# OSPLC2_2_IO1.net
KiCad netlist of a schematic drawn in Altium Designer
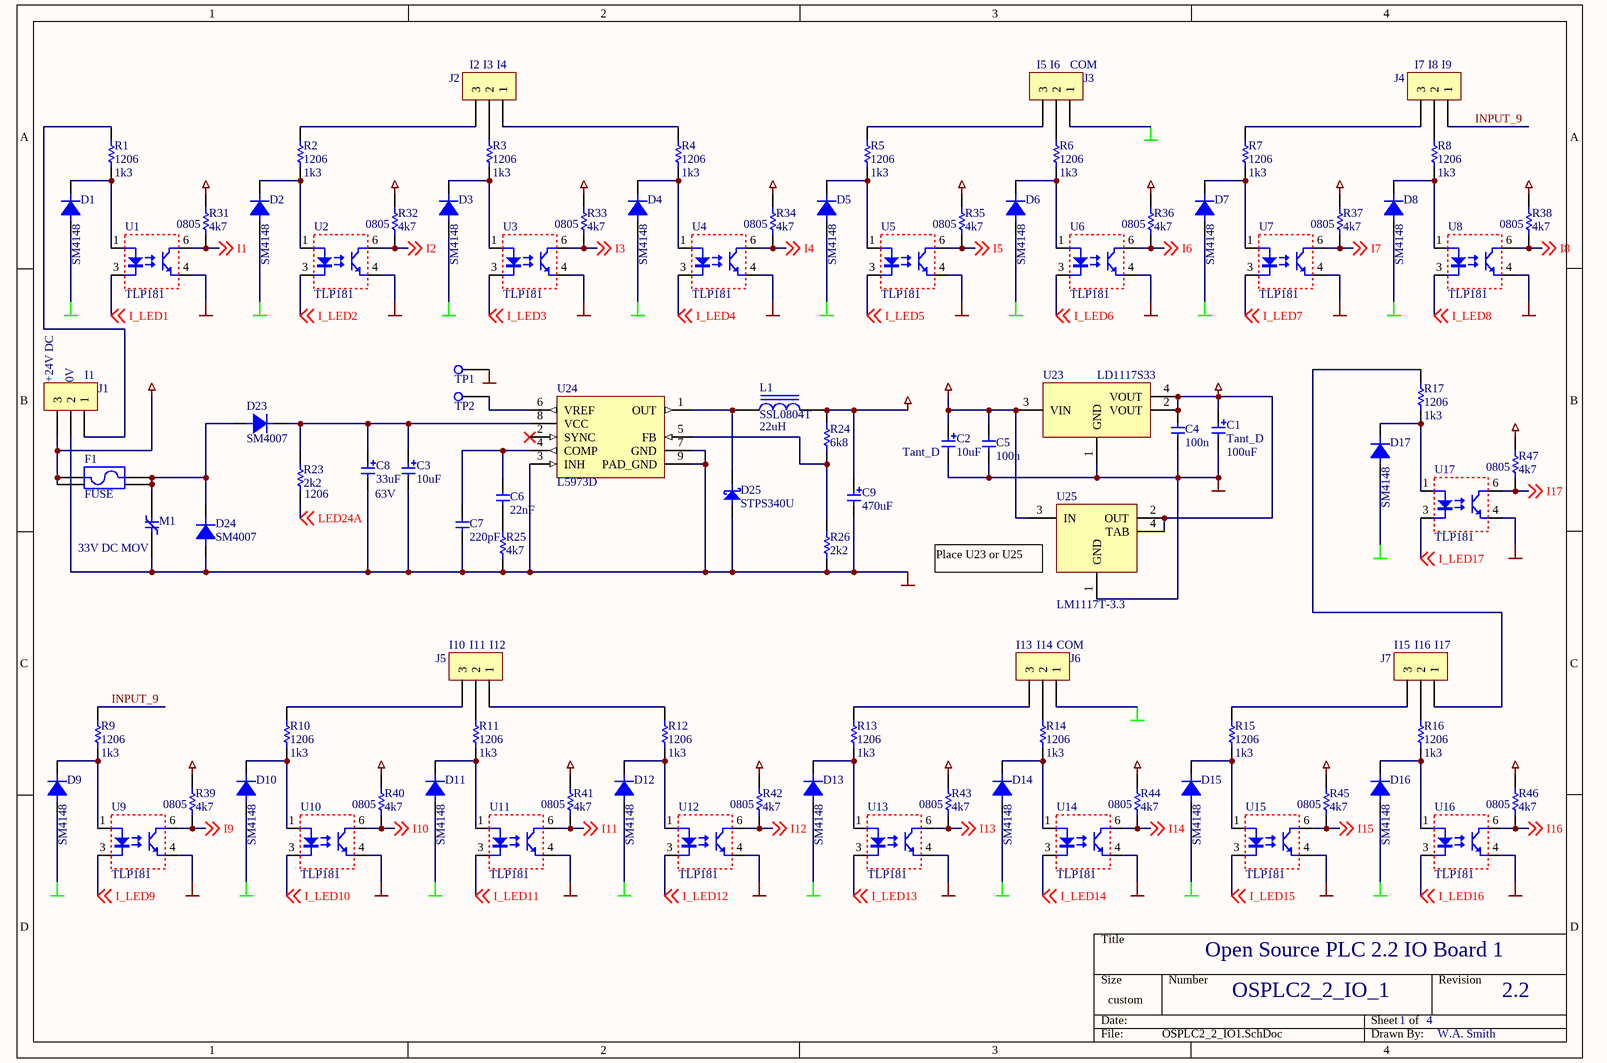
[diagram p0: OSPLC2_2_IO1.SchDoc]

(export (version "E")
  (design (tool "Eeschema 10.0.6"))
  (components
    (comp (ref "C1")
      (value "Tant_D")
      (footprint "CAP_TANT_D")
      (description "Tantalum Capacitor, D package")
      (fields (field (name "ALTIUM_VALUE") "100uF"))
      (libsource (lib "Integrated Comp_lib") (part "CAP_TANT_D"))
    )
    (comp (ref "C2")
      (value "Tant_D")
      (footprint "CAP_TANT_D")
      (description "Tantalum Capacitor, D package")
      (fields (field (name "ALTIUM_VALUE") "10uF"))
      (libsource (lib "Integrated Comp_lib") (part "CAP_TANT_D"))
    )
    (comp (ref "C3")
      (value "CAP_100_RP")
      (footprint "CAP_100_RP")
      (description "Electrolytic cap, 100 mil pitch")
      (fields (field (name "ALTIUM_VALUE") "10uF"))
      (libsource (lib "Integrated Comp_lib") (part "CAP_100_RP"))
    )
    (comp (ref "C4")
      (value "0805")
      (footprint "0805")
      (description "0805 footprint non-polarised capacitor")
      (fields (field (name "ALTIUM_VALUE") "100n"))
      (libsource (lib "Integrated Comp_lib") (part "CAP_0805"))
    )
    (comp (ref "C5")
      (value "0805")
      (footprint "0805")
      (description "0805 footprint non-polarised capacitor")
      (fields (field (name "ALTIUM_VALUE") "100n"))
      (libsource (lib "Integrated Comp_lib") (part "CAP_0805"))
    )
    (comp (ref "C6")
      (value "0805")
      (footprint "0805")
      (description "0805 footprint non-polarised capacitor")
      (fields (field (name "ALTIUM_VALUE") "22nF"))
      (libsource (lib "Integrated Comp_lib") (part "CAP_0805"))
    )
    (comp (ref "C7")
      (value "0805")
      (footprint "0805")
      (description "0805 footprint non-polarised capacitor")
      (fields (field (name "ALTIUM_VALUE") "220pF"))
      (libsource (lib "Integrated Comp_lib") (part "CAP_0805"))
    )
    (comp (ref "C8")
      (value "63V")
      (footprint "CAP_100_RP")
      (description "Electrolytic cap, 100 mil pitch")
      (fields (field (name "ALTIUM_VALUE") "33uF"))
      (libsource (lib "Integrated Comp_lib") (part "CAP_100_RP"))
    )
    (comp (ref "C9")
      (value "CAP_200_RP")
      (footprint "CAP_200_RP")
      (description "Radial Electrolytic Capacitor, 200 thou pin spacing")
      (fields (field (name "ALTIUM_VALUE") "470uF"))
      (libsource (lib "Integrated Comp_lib") (part "CAP_200_RP"))
    )
    (comp (ref "D1")
      (value "SM4148")
      (footprint "MELF-R2/X1.6")
      (description "SMT 1N4148 diode")
      (libsource (lib "ARM_projects") (part "SM4148"))
    )
    (comp (ref "D2")
      (value "SM4148")
      (footprint "MELF-R2/X1.6")
      (description "SMT 1N4148 diode")
      (libsource (lib "ARM_projects") (part "SM4148"))
    )
    (comp (ref "D3")
      (value "SM4148")
      (footprint "MELF-R2/X1.6")
      (description "SMT 1N4148 diode")
      (libsource (lib "ARM_projects") (part "SM4148"))
    )
    (comp (ref "D4")
      (value "SM4148")
      (footprint "MELF-R2/X1.6")
      (description "SMT 1N4148 diode")
      (libsource (lib "ARM_projects") (part "SM4148"))
    )
    (comp (ref "D5")
      (value "SM4148")
      (footprint "MELF-R2/X1.6")
      (description "SMT 1N4148 diode")
      (libsource (lib "ARM_projects") (part "SM4148"))
    )
    (comp (ref "D6")
      (value "SM4148")
      (footprint "MELF-R2/X1.6")
      (description "SMT 1N4148 diode")
      (libsource (lib "ARM_projects") (part "SM4148"))
    )
    (comp (ref "D7")
      (value "SM4148")
      (footprint "MELF-R2/X1.6")
      (description "SMT 1N4148 diode")
      (libsource (lib "ARM_projects") (part "SM4148"))
    )
    (comp (ref "D8")
      (value "SM4148")
      (footprint "MELF-R2/X1.6")
      (description "SMT 1N4148 diode")
      (libsource (lib "ARM_projects") (part "SM4148"))
    )
    (comp (ref "D9")
      (value "SM4148")
      (footprint "MELF-R2/X1.6")
      (description "SMT 1N4148 diode")
      (libsource (lib "ARM_projects") (part "SM4148"))
    )
    (comp (ref "D10")
      (value "SM4148")
      (footprint "MELF-R2/X1.6")
      (description "SMT 1N4148 diode")
      (libsource (lib "ARM_projects") (part "SM4148"))
    )
    (comp (ref "D11")
      (value "SM4148")
      (footprint "MELF-R2/X1.6")
      (description "SMT 1N4148 diode")
      (libsource (lib "ARM_projects") (part "SM4148"))
    )
    (comp (ref "D12")
      (value "SM4148")
      (footprint "MELF-R2/X1.6")
      (description "SMT 1N4148 diode")
      (libsource (lib "ARM_projects") (part "SM4148"))
    )
    (comp (ref "D13")
      (value "SM4148")
      (footprint "MELF-R2/X1.6")
      (description "SMT 1N4148 diode")
      (libsource (lib "ARM_projects") (part "SM4148"))
    )
    (comp (ref "D14")
      (value "SM4148")
      (footprint "MELF-R2/X1.6")
      (description "SMT 1N4148 diode")
      (libsource (lib "ARM_projects") (part "SM4148"))
    )
    (comp (ref "D15")
      (value "SM4148")
      (footprint "MELF-R2/X1.6")
      (description "SMT 1N4148 diode")
      (libsource (lib "ARM_projects") (part "SM4148"))
    )
    (comp (ref "D16")
      (value "SM4148")
      (footprint "MELF-R2/X1.6")
      (description "SMT 1N4148 diode")
      (libsource (lib "ARM_projects") (part "SM4148"))
    )
    (comp (ref "D17")
      (value "SM4148")
      (footprint "MELF-R2/X1.6")
      (description "SMT 1N4148 diode")
      (libsource (lib "ARM_projects") (part "SM4148"))
    )
    (comp (ref "D23")
      (value "SM4007")
      (footprint "MELF-2.2x2.5")
      (description "1A, 1000V MELF Rectifier")
      (libsource (lib "ARM_projects") (part "SM4007"))
    )
    (comp (ref "D24")
      (value "SM4007")
      (footprint "MELF-2.2x2.5")
      (description "1A, 1000V MELF Rectifier")
      (libsource (lib "ARM_projects") (part "SM4007"))
    )
    (comp (ref "D25")
      (value "STPS340U")
      (footprint "STPS2L25U")
      (description "Power Schottky rectifier, ST")
      (libsource (lib "ARM_projects") (part "STPS340U"))
    )
    (comp (ref "F1")
      (value "FUSE")
      (footprint "FUSE_MULT")
      (description "Fuse holder or Fuse clips for 20mm fuse")
      (libsource (lib "ARM_projects") (part "FUSE_MULTI"))
    )
    (comp (ref "J1")
      (value "PCB TERMINAL")
      (footprint "TERMINAL_3WAY_5MM")
      (description "5mm spaced PCB terminal, 3 pole")
      (libsource (lib "ARM_projects") (part "TERMINAL_3WAY_5MM"))
    )
    (comp (ref "J2")
      (value "PCB TERMINAL")
      (footprint "TERMINAL_3WAY_5MM")
      (description "5mm spaced PCB terminal, 3 pole")
      (libsource (lib "ARM_projects") (part "TERMINAL_3WAY_5MM"))
    )
    (comp (ref "J3")
      (value "PCB TERMINAL")
      (footprint "TERMINAL_3WAY_5MM")
      (description "5mm spaced PCB terminal, 3 pole")
      (libsource (lib "ARM_projects") (part "TERMINAL_3WAY_5MM"))
    )
    (comp (ref "J4")
      (value "PCB TERMINAL")
      (footprint "TERMINAL_3WAY_5MM")
      (description "5mm spaced PCB terminal, 3 pole")
      (libsource (lib "ARM_projects") (part "TERMINAL_3WAY_5MM"))
    )
    (comp (ref "J5")
      (value "PCB TERMINAL")
      (footprint "TERMINAL_3WAY_5MM")
      (description "5mm spaced PCB terminal, 3 pole")
      (libsource (lib "ARM_projects") (part "TERMINAL_3WAY_5MM"))
    )
    (comp (ref "J6")
      (value "PCB TERMINAL")
      (footprint "TERMINAL_3WAY_5MM")
      (description "5mm spaced PCB terminal, 3 pole")
      (libsource (lib "ARM_projects") (part "TERMINAL_3WAY_5MM"))
    )
    (comp (ref "J7")
      (value "PCB TERMINAL")
      (footprint "TERMINAL_3WAY_5MM")
      (description "5mm spaced PCB terminal, 3 pole")
      (libsource (lib "ARM_projects") (part "TERMINAL_3WAY_5MM"))
    )
    (comp (ref "L1")
      (value "SSL0804T")
      (footprint "SSL0804")
      (description "Yageo SMD Power Inductor")
      (fields (field (name "ALTIUM_UNNAMED_1") "22uH"))
      (libsource (lib "ARM_projects") (part "SSL0804T"))
    )
    (comp (ref "M1")
      (value "33V DC MOV")
      (footprint "MOV_7.6mm")
      (description "Metal Oxide Varistor")
      (libsource (lib "ARM_projects") (part "MOV_7.6MM"))
    )
    (comp (ref "R1")
      (value "1206")
      (footprint "1206")
      (description "1206 footprint resistor")
      (fields (field (name "ALTIUM_VALUE") "1k3"))
      (libsource (lib "Integrated Comp_lib") (part "RES_1206"))
    )
    (comp (ref "R2")
      (value "1206")
      (footprint "1206")
      (description "1206 footprint resistor")
      (fields (field (name "ALTIUM_VALUE") "1k3"))
      (libsource (lib "Integrated Comp_lib") (part "RES_1206"))
    )
    (comp (ref "R3")
      (value "1206")
      (footprint "1206")
      (description "1206 footprint resistor")
      (fields (field (name "ALTIUM_VALUE") "1k3"))
      (libsource (lib "Integrated Comp_lib") (part "RES_1206"))
    )
    (comp (ref "R4")
      (value "1206")
      (footprint "1206")
      (description "1206 footprint resistor")
      (fields (field (name "ALTIUM_VALUE") "1k3"))
      (libsource (lib "Integrated Comp_lib") (part "RES_1206"))
    )
    (comp (ref "R5")
      (value "1206")
      (footprint "1206")
      (description "1206 footprint resistor")
      (fields (field (name "ALTIUM_VALUE") "1k3"))
      (libsource (lib "Integrated Comp_lib") (part "RES_1206"))
    )
    (comp (ref "R6")
      (value "1206")
      (footprint "1206")
      (description "1206 footprint resistor")
      (fields (field (name "ALTIUM_VALUE") "1k3"))
      (libsource (lib "Integrated Comp_lib") (part "RES_1206"))
    )
    (comp (ref "R7")
      (value "1206")
      (footprint "1206")
      (description "1206 footprint resistor")
      (fields (field (name "ALTIUM_VALUE") "1k3"))
      (libsource (lib "Integrated Comp_lib") (part "RES_1206"))
    )
    (comp (ref "R8")
      (value "1206")
      (footprint "1206")
      (description "1206 footprint resistor")
      (fields (field (name "ALTIUM_VALUE") "1k3"))
      (libsource (lib "Integrated Comp_lib") (part "RES_1206"))
    )
    (comp (ref "R9")
      (value "1206")
      (footprint "1206")
      (description "1206 footprint resistor")
      (fields (field (name "ALTIUM_VALUE") "1k3"))
      (libsource (lib "Integrated Comp_lib") (part "RES_1206"))
    )
    (comp (ref "R10")
      (value "1206")
      (footprint "1206")
      (description "1206 footprint resistor")
      (fields (field (name "ALTIUM_VALUE") "1k3"))
      (libsource (lib "Integrated Comp_lib") (part "RES_1206"))
    )
    (comp (ref "R11")
      (value "1206")
      (footprint "1206")
      (description "1206 footprint resistor")
      (fields (field (name "ALTIUM_VALUE") "1k3"))
      (libsource (lib "Integrated Comp_lib") (part "RES_1206"))
    )
    (comp (ref "R12")
      (value "1206")
      (footprint "1206")
      (description "1206 footprint resistor")
      (fields (field (name "ALTIUM_VALUE") "1k3"))
      (libsource (lib "Integrated Comp_lib") (part "RES_1206"))
    )
    (comp (ref "R13")
      (value "1206")
      (footprint "1206")
      (description "1206 footprint resistor")
      (fields (field (name "ALTIUM_VALUE") "1k3"))
      (libsource (lib "Integrated Comp_lib") (part "RES_1206"))
    )
    (comp (ref "R14")
      (value "1206")
      (footprint "1206")
      (description "1206 footprint resistor")
      (fields (field (name "ALTIUM_VALUE") "1k3"))
      (libsource (lib "Integrated Comp_lib") (part "RES_1206"))
    )
    (comp (ref "R15")
      (value "1206")
      (footprint "1206")
      (description "1206 footprint resistor")
      (fields (field (name "ALTIUM_VALUE") "1k3"))
      (libsource (lib "Integrated Comp_lib") (part "RES_1206"))
    )
    (comp (ref "R16")
      (value "1206")
      (footprint "1206")
      (description "1206 footprint resistor")
      (fields (field (name "ALTIUM_VALUE") "1k3"))
      (libsource (lib "Integrated Comp_lib") (part "RES_1206"))
    )
    (comp (ref "R17")
      (value "1206")
      (footprint "1206")
      (description "1206 footprint resistor")
      (fields (field (name "ALTIUM_VALUE") "1k3"))
      (libsource (lib "Integrated Comp_lib") (part "RES_1206"))
    )
    (comp (ref "R23")
      (value "1206")
      (footprint "1206")
      (description "1206 footprint resistor")
      (fields (field (name "ALTIUM_VALUE") "2k2"))
      (libsource (lib "Integrated Comp_lib") (part "RES_1206"))
    )
    (comp (ref "R24")
      (value "0805")
      (footprint "0805")
      (description "0805 footprint resistor")
      (fields (field (name "ALTIUM_VALUE") "6k8"))
      (libsource (lib "Integrated Comp_lib") (part "RES_0805"))
    )
    (comp (ref "R25")
      (value "0805")
      (footprint "0805")
      (description "0805 footprint resistor")
      (fields (field (name "ALTIUM_VALUE") "4k7"))
      (libsource (lib "Integrated Comp_lib") (part "RES_0805"))
    )
    (comp (ref "R26")
      (value "0805")
      (footprint "0805")
      (description "0805 footprint resistor")
      (fields (field (name "ALTIUM_VALUE") "2k2"))
      (libsource (lib "Integrated Comp_lib") (part "RES_0805"))
    )
    (comp (ref "R31")
      (value "0805")
      (footprint "0805")
      (description "0805 footprint resistor")
      (fields (field (name "ALTIUM_VALUE") "4k7"))
      (libsource (lib "Integrated Comp_lib") (part "RES_0805"))
    )
    (comp (ref "R32")
      (value "0805")
      (footprint "0805")
      (description "0805 footprint resistor")
      (fields (field (name "ALTIUM_VALUE") "4k7"))
      (libsource (lib "Integrated Comp_lib") (part "RES_0805"))
    )
    (comp (ref "R33")
      (value "0805")
      (footprint "0805")
      (description "0805 footprint resistor")
      (fields (field (name "ALTIUM_VALUE") "4k7"))
      (libsource (lib "Integrated Comp_lib") (part "RES_0805"))
    )
    (comp (ref "R34")
      (value "0805")
      (footprint "0805")
      (description "0805 footprint resistor")
      (fields (field (name "ALTIUM_VALUE") "4k7"))
      (libsource (lib "Integrated Comp_lib") (part "RES_0805"))
    )
    (comp (ref "R35")
      (value "0805")
      (footprint "0805")
      (description "0805 footprint resistor")
      (fields (field (name "ALTIUM_VALUE") "4k7"))
      (libsource (lib "Integrated Comp_lib") (part "RES_0805"))
    )
    (comp (ref "R36")
      (value "0805")
      (footprint "0805")
      (description "0805 footprint resistor")
      (fields (field (name "ALTIUM_VALUE") "4k7"))
      (libsource (lib "Integrated Comp_lib") (part "RES_0805"))
    )
    (comp (ref "R37")
      (value "0805")
      (footprint "0805")
      (description "0805 footprint resistor")
      (fields (field (name "ALTIUM_VALUE") "4k7"))
      (libsource (lib "Integrated Comp_lib") (part "RES_0805"))
    )
    (comp (ref "R38")
      (value "0805")
      (footprint "0805")
      (description "0805 footprint resistor")
      (fields (field (name "ALTIUM_VALUE") "4k7"))
      (libsource (lib "Integrated Comp_lib") (part "RES_0805"))
    )
    (comp (ref "R39")
      (value "0805")
      (footprint "0805")
      (description "0805 footprint resistor")
      (fields (field (name "ALTIUM_VALUE") "4k7"))
      (libsource (lib "Integrated Comp_lib") (part "RES_0805"))
    )
    (comp (ref "R40")
      (value "0805")
      (footprint "0805")
      (description "0805 footprint resistor")
      (fields (field (name "ALTIUM_VALUE") "4k7"))
      (libsource (lib "Integrated Comp_lib") (part "RES_0805"))
    )
    (comp (ref "R41")
      (value "0805")
      (footprint "0805")
      (description "0805 footprint resistor")
      (fields (field (name "ALTIUM_VALUE") "4k7"))
      (libsource (lib "Integrated Comp_lib") (part "RES_0805"))
    )
    (comp (ref "R42")
      (value "0805")
      (footprint "0805")
      (description "0805 footprint resistor")
      (fields (field (name "ALTIUM_VALUE") "4k7"))
      (libsource (lib "Integrated Comp_lib") (part "RES_0805"))
    )
    (comp (ref "R43")
      (value "0805")
      (footprint "0805")
      (description "0805 footprint resistor")
      (fields (field (name "ALTIUM_VALUE") "4k7"))
      (libsource (lib "Integrated Comp_lib") (part "RES_0805"))
    )
    (comp (ref "R44")
      (value "0805")
      (footprint "0805")
      (description "0805 footprint resistor")
      (fields (field (name "ALTIUM_VALUE") "4k7"))
      (libsource (lib "Integrated Comp_lib") (part "RES_0805"))
    )
    (comp (ref "R45")
      (value "0805")
      (footprint "0805")
      (description "0805 footprint resistor")
      (fields (field (name "ALTIUM_VALUE") "4k7"))
      (libsource (lib "Integrated Comp_lib") (part "RES_0805"))
    )
    (comp (ref "R46")
      (value "0805")
      (footprint "0805")
      (description "0805 footprint resistor")
      (fields (field (name "ALTIUM_VALUE") "4k7"))
      (libsource (lib "Integrated Comp_lib") (part "RES_0805"))
    )
    (comp (ref "R47")
      (value "0805")
      (footprint "0805")
      (description "0805 footprint resistor")
      (fields (field (name "ALTIUM_VALUE") "4k7"))
      (libsource (lib "Integrated Comp_lib") (part "RES_0805"))
    )
    (comp (ref "TP1")
      (value "TEST POINT")
      (footprint "TEST_POINT_TH")
      (description "Through hole test point")
      (libsource (lib "ARM_projects") (part "TEST_POINT_TH"))
    )
    (comp (ref "TP2")
      (value "TEST POINT")
      (footprint "TEST_POINT_TH")
      (description "Through hole test point")
      (libsource (lib "ARM_projects") (part "TEST_POINT_TH"))
    )
    (comp (ref "U1")
      (value "TLP181")
      (footprint "SOP4_2.54")
      (description "Toshiba Photocoupler")
      (libsource (lib "Integrated Comp_lib") (part "TLP181"))
    )
    (comp (ref "U2")
      (value "TLP181")
      (footprint "SOP4_2.54")
      (description "Toshiba Photocoupler")
      (libsource (lib "Integrated Comp_lib") (part "TLP181"))
    )
    (comp (ref "U3")
      (value "TLP181")
      (footprint "SOP4_2.54")
      (description "Toshiba Photocoupler")
      (libsource (lib "Integrated Comp_lib") (part "TLP181"))
    )
    (comp (ref "U4")
      (value "TLP181")
      (footprint "SOP4_2.54")
      (description "Toshiba Photocoupler")
      (libsource (lib "Integrated Comp_lib") (part "TLP181"))
    )
    (comp (ref "U5")
      (value "TLP181")
      (footprint "SOP4_2.54")
      (description "Toshiba Photocoupler")
      (libsource (lib "Integrated Comp_lib") (part "TLP181"))
    )
    (comp (ref "U6")
      (value "TLP181")
      (footprint "SOP4_2.54")
      (description "Toshiba Photocoupler")
      (libsource (lib "Integrated Comp_lib") (part "TLP181"))
    )
    (comp (ref "U7")
      (value "TLP181")
      (footprint "SOP4_2.54")
      (description "Toshiba Photocoupler")
      (libsource (lib "Integrated Comp_lib") (part "TLP181"))
    )
    (comp (ref "U8")
      (value "TLP181")
      (footprint "SOP4_2.54")
      (description "Toshiba Photocoupler")
      (libsource (lib "Integrated Comp_lib") (part "TLP181"))
    )
    (comp (ref "U9")
      (value "TLP181")
      (footprint "SOP4_2.54")
      (description "Toshiba Photocoupler")
      (libsource (lib "Integrated Comp_lib") (part "TLP181"))
    )
    (comp (ref "U10")
      (value "TLP181")
      (footprint "SOP4_2.54")
      (description "Toshiba Photocoupler")
      (libsource (lib "Integrated Comp_lib") (part "TLP181"))
    )
    (comp (ref "U11")
      (value "TLP181")
      (footprint "SOP4_2.54")
      (description "Toshiba Photocoupler")
      (libsource (lib "Integrated Comp_lib") (part "TLP181"))
    )
    (comp (ref "U12")
      (value "TLP181")
      (footprint "SOP4_2.54")
      (description "Toshiba Photocoupler")
      (libsource (lib "Integrated Comp_lib") (part "TLP181"))
    )
    (comp (ref "U13")
      (value "TLP181")
      (footprint "SOP4_2.54")
      (description "Toshiba Photocoupler")
      (libsource (lib "Integrated Comp_lib") (part "TLP181"))
    )
    (comp (ref "U14")
      (value "TLP181")
      (footprint "SOP4_2.54")
      (description "Toshiba Photocoupler")
      (libsource (lib "Integrated Comp_lib") (part "TLP181"))
    )
    (comp (ref "U15")
      (value "TLP181")
      (footprint "SOP4_2.54")
      (description "Toshiba Photocoupler")
      (libsource (lib "Integrated Comp_lib") (part "TLP181"))
    )
    (comp (ref "U16")
      (value "TLP181")
      (footprint "SOP4_2.54")
      (description "Toshiba Photocoupler")
      (libsource (lib "Integrated Comp_lib") (part "TLP181"))
    )
    (comp (ref "U17")
      (value "TLP181")
      (footprint "SOP4_2.54")
      (description "Toshiba Photocoupler")
      (libsource (lib "Integrated Comp_lib") (part "TLP181"))
    )
    (comp (ref "U23")
      (value "LD1117S33")
      (footprint "SOT-223")
      (description "ST 3.3V LDO regulator")
      (libsource (lib "ARM_projects") (part "LD1117S33"))
    )
    (comp (ref "U24")
      (value "L5973D")
      (footprint "ARM_projects:HSOP8")
      (description "ST 2.5A switch step down switching regulator")
      (libsource (lib "ARM_projects") (part "L5973D"))
    )
    (comp (ref "U25")
      (value "LM1117T-3.3")
      (footprint "TO-220_H")
      (description "National  800mA LDO regulator")
      (libsource (lib "Integrated Comp_lib") (part "LM1117T-3.3"))
    )
  )
  (nets
    (net (code "1") (name "/INPUT_9") (class "Default")
      (node (ref "J4") (pin "1") (pinfunction "1_1") (pintype "passive"))
      (node (ref "R9") (pin "2") (pinfunction "2_2") (pintype "passive"))
    )
    (net (code "2") (name "GND") (class "Default")
      (node (ref "C1") (pin "2") (pinfunction "2_2") (pintype "passive"))
      (node (ref "C2") (pin "2") (pinfunction "2_2") (pintype "passive"))
      (node (ref "C3") (pin "2") (pinfunction "2_2") (pintype "passive"))
      (node (ref "C4") (pin "2") (pinfunction "2_2") (pintype "passive"))
      (node (ref "C5") (pin "2") (pinfunction "2_2") (pintype "passive"))
      (node (ref "C7") (pin "1") (pinfunction "1_1") (pintype "passive"))
      (node (ref "C8") (pin "2") (pinfunction "2_2") (pintype "passive"))
      (node (ref "C9") (pin "2") (pinfunction "2_2") (pintype "passive"))
      (node (ref "D24") (pin "1") (pinfunction "A_1") (pintype "passive"))
      (node (ref "D25") (pin "2") (pinfunction "A_2") (pintype "passive"))
      (node (ref "J1") (pin "2") (pinfunction "2_2") (pintype "passive"))
      (node (ref "M1") (pin "1") (pinfunction "1_1") (pintype "passive"))
      (node (ref "R25") (pin "1") (pinfunction "1_1") (pintype "passive"))
      (node (ref "R26") (pin "1") (pinfunction "1_1") (pintype "passive"))
      (node (ref "TP1") (pin "1") (pinfunction "1_1") (pintype "passive"))
      (node (ref "U1") (pin "4") (pinfunction "4_4") (pintype "passive"))
      (node (ref "U10") (pin "4") (pinfunction "4_4") (pintype "passive"))
      (node (ref "U11") (pin "4") (pinfunction "4_4") (pintype "passive"))
      (node (ref "U12") (pin "4") (pinfunction "4_4") (pintype "passive"))
      (node (ref "U13") (pin "4") (pinfunction "4_4") (pintype "passive"))
      (node (ref "U14") (pin "4") (pinfunction "4_4") (pintype "passive"))
      (node (ref "U15") (pin "4") (pinfunction "4_4") (pintype "passive"))
      (node (ref "U16") (pin "4") (pinfunction "4_4") (pintype "passive"))
      (node (ref "U17") (pin "4") (pinfunction "4_4") (pintype "passive"))
      (node (ref "U2") (pin "4") (pinfunction "4_4") (pintype "passive"))
      (node (ref "U23") (pin "1") (pinfunction "GND_1") (pintype "power_in"))
      (node (ref "U24") (pin "3") (pinfunction "INH_3") (pintype "input"))
      (node (ref "U24") (pin "7") (pinfunction "GND_7") (pintype "power_in"))
      (node (ref "U24") (pin "9") (pinfunction "PAD_GND_9") (pintype "power_in"))
      (node (ref "U25") (pin "1") (pinfunction "GND_1") (pintype "power_in"))
      (node (ref "U3") (pin "4") (pinfunction "4_4") (pintype "passive"))
      (node (ref "U4") (pin "4") (pinfunction "4_4") (pintype "passive"))
      (node (ref "U5") (pin "4") (pinfunction "4_4") (pintype "passive"))
      (node (ref "U6") (pin "4") (pinfunction "4_4") (pintype "passive"))
      (node (ref "U7") (pin "4") (pinfunction "4_4") (pintype "passive"))
      (node (ref "U8") (pin "4") (pinfunction "4_4") (pintype "passive"))
      (node (ref "U9") (pin "4") (pinfunction "4_4") (pintype "passive"))
    )
    (net (code "3") (name "I1") (class "Default")
      (node (ref "R31") (pin "1") (pinfunction "1_1") (pintype "passive"))
      (node (ref "U1") (pin "6") (pinfunction "6_6") (pintype "passive"))
    )
    (net (code "4") (name "I2") (class "Default")
      (node (ref "R32") (pin "1") (pinfunction "1_1") (pintype "passive"))
      (node (ref "U2") (pin "6") (pinfunction "6_6") (pintype "passive"))
    )
    (net (code "5") (name "I3") (class "Default")
      (node (ref "R33") (pin "1") (pinfunction "1_1") (pintype "passive"))
      (node (ref "U3") (pin "6") (pinfunction "6_6") (pintype "passive"))
    )
    (net (code "6") (name "I4") (class "Default")
      (node (ref "R34") (pin "1") (pinfunction "1_1") (pintype "passive"))
      (node (ref "U4") (pin "6") (pinfunction "6_6") (pintype "passive"))
    )
    (net (code "7") (name "I5") (class "Default")
      (node (ref "R35") (pin "1") (pinfunction "1_1") (pintype "passive"))
      (node (ref "U5") (pin "6") (pinfunction "6_6") (pintype "passive"))
    )
    (net (code "8") (name "I6") (class "Default")
      (node (ref "R36") (pin "1") (pinfunction "1_1") (pintype "passive"))
      (node (ref "U6") (pin "6") (pinfunction "6_6") (pintype "passive"))
    )
    (net (code "9") (name "I7") (class "Default")
      (node (ref "R37") (pin "1") (pinfunction "1_1") (pintype "passive"))
      (node (ref "U7") (pin "6") (pinfunction "6_6") (pintype "passive"))
    )
    (net (code "10") (name "I8") (class "Default")
      (node (ref "R38") (pin "1") (pinfunction "1_1") (pintype "passive"))
      (node (ref "U8") (pin "6") (pinfunction "6_6") (pintype "passive"))
    )
    (net (code "11") (name "I9") (class "Default")
      (node (ref "R39") (pin "1") (pinfunction "1_1") (pintype "passive"))
      (node (ref "U9") (pin "6") (pinfunction "6_6") (pintype "passive"))
    )
    (net (code "12") (name "I10") (class "Default")
      (node (ref "R40") (pin "1") (pinfunction "1_1") (pintype "passive"))
      (node (ref "U10") (pin "6") (pinfunction "6_6") (pintype "passive"))
    )
    (net (code "13") (name "I11") (class "Default")
      (node (ref "R41") (pin "1") (pinfunction "1_1") (pintype "passive"))
      (node (ref "U11") (pin "6") (pinfunction "6_6") (pintype "passive"))
    )
    (net (code "14") (name "I12") (class "Default")
      (node (ref "R42") (pin "1") (pinfunction "1_1") (pintype "passive"))
      (node (ref "U12") (pin "6") (pinfunction "6_6") (pintype "passive"))
    )
    (net (code "15") (name "I13") (class "Default")
      (node (ref "R43") (pin "1") (pinfunction "1_1") (pintype "passive"))
      (node (ref "U13") (pin "6") (pinfunction "6_6") (pintype "passive"))
    )
    (net (code "16") (name "I14") (class "Default")
      (node (ref "R44") (pin "1") (pinfunction "1_1") (pintype "passive"))
      (node (ref "U14") (pin "6") (pinfunction "6_6") (pintype "passive"))
    )
    (net (code "17") (name "I15") (class "Default")
      (node (ref "R45") (pin "1") (pinfunction "1_1") (pintype "passive"))
      (node (ref "U15") (pin "6") (pinfunction "6_6") (pintype "passive"))
    )
    (net (code "18") (name "I16") (class "Default")
      (node (ref "R46") (pin "1") (pinfunction "1_1") (pintype "passive"))
      (node (ref "U16") (pin "6") (pinfunction "6_6") (pintype "passive"))
    )
    (net (code "19") (name "I17") (class "Default")
      (node (ref "R47") (pin "1") (pinfunction "1_1") (pintype "passive"))
      (node (ref "U17") (pin "6") (pinfunction "6_6") (pintype "passive"))
    )
    (net (code "20") (name "IN_GND") (class "Default")
      (node (ref "D1") (pin "1") (pinfunction "A_1") (pintype "passive"))
      (node (ref "D10") (pin "1") (pinfunction "A_1") (pintype "passive"))
      (node (ref "D11") (pin "1") (pinfunction "A_1") (pintype "passive"))
      (node (ref "D12") (pin "1") (pinfunction "A_1") (pintype "passive"))
      (node (ref "D13") (pin "1") (pinfunction "A_1") (pintype "passive"))
      (node (ref "D14") (pin "1") (pinfunction "A_1") (pintype "passive"))
      (node (ref "D15") (pin "1") (pinfunction "A_1") (pintype "passive"))
      (node (ref "D16") (pin "1") (pinfunction "A_1") (pintype "passive"))
      (node (ref "D17") (pin "1") (pinfunction "A_1") (pintype "passive"))
      (node (ref "D2") (pin "1") (pinfunction "A_1") (pintype "passive"))
      (node (ref "D3") (pin "1") (pinfunction "A_1") (pintype "passive"))
      (node (ref "D4") (pin "1") (pinfunction "A_1") (pintype "passive"))
      (node (ref "D5") (pin "1") (pinfunction "A_1") (pintype "passive"))
      (node (ref "D6") (pin "1") (pinfunction "A_1") (pintype "passive"))
      (node (ref "D7") (pin "1") (pinfunction "A_1") (pintype "passive"))
      (node (ref "D8") (pin "1") (pinfunction "A_1") (pintype "passive"))
      (node (ref "D9") (pin "1") (pinfunction "A_1") (pintype "passive"))
      (node (ref "J3") (pin "1") (pinfunction "1_1") (pintype "passive"))
      (node (ref "J6") (pin "1") (pinfunction "1_1") (pintype "passive"))
    )
    (net (code "21") (name "I_LED1") (class "Default")
      (node (ref "U1") (pin "3") (pinfunction "3_3") (pintype "passive"))
    )
    (net (code "22") (name "I_LED2") (class "Default")
      (node (ref "U2") (pin "3") (pinfunction "3_3") (pintype "passive"))
    )
    (net (code "23") (name "I_LED3") (class "Default")
      (node (ref "U3") (pin "3") (pinfunction "3_3") (pintype "passive"))
    )
    (net (code "24") (name "I_LED4") (class "Default")
      (node (ref "U4") (pin "3") (pinfunction "3_3") (pintype "passive"))
    )
    (net (code "25") (name "I_LED5") (class "Default")
      (node (ref "U5") (pin "3") (pinfunction "3_3") (pintype "passive"))
    )
    (net (code "26") (name "I_LED6") (class "Default")
      (node (ref "U6") (pin "3") (pinfunction "3_3") (pintype "passive"))
    )
    (net (code "27") (name "I_LED7") (class "Default")
      (node (ref "U7") (pin "3") (pinfunction "3_3") (pintype "passive"))
    )
    (net (code "28") (name "I_LED8") (class "Default")
      (node (ref "U8") (pin "3") (pinfunction "3_3") (pintype "passive"))
    )
    (net (code "29") (name "I_LED9") (class "Default")
      (node (ref "U9") (pin "3") (pinfunction "3_3") (pintype "passive"))
    )
    (net (code "30") (name "I_LED10") (class "Default")
      (node (ref "U10") (pin "3") (pinfunction "3_3") (pintype "passive"))
    )
    (net (code "31") (name "I_LED11") (class "Default")
      (node (ref "U11") (pin "3") (pinfunction "3_3") (pintype "passive"))
    )
    (net (code "32") (name "I_LED12") (class "Default")
      (node (ref "U12") (pin "3") (pinfunction "3_3") (pintype "passive"))
    )
    (net (code "33") (name "I_LED13") (class "Default")
      (node (ref "U13") (pin "3") (pinfunction "3_3") (pintype "passive"))
    )
    (net (code "34") (name "I_LED14") (class "Default")
      (node (ref "U14") (pin "3") (pinfunction "3_3") (pintype "passive"))
    )
    (net (code "35") (name "I_LED15") (class "Default")
      (node (ref "U15") (pin "3") (pinfunction "3_3") (pintype "passive"))
    )
    (net (code "36") (name "I_LED16") (class "Default")
      (node (ref "U16") (pin "3") (pinfunction "3_3") (pintype "passive"))
    )
    (net (code "37") (name "I_LED17") (class "Default")
      (node (ref "U17") (pin "3") (pinfunction "3_3") (pintype "passive"))
    )
    (net (code "38") (name "LED24A") (class "Default")
      (node (ref "R23") (pin "1") (pinfunction "1_1") (pintype "passive"))
    )
    (net (code "39") (name "Net-(C6-Pad1)") (class "Default")
      (node (ref "C6") (pin "1") (pinfunction "1_1") (pintype "passive"))
      (node (ref "R25") (pin "2") (pinfunction "2_2") (pintype "passive"))
    )
    (net (code "40") (name "Net-(D1-C)") (class "Default")
      (node (ref "D1") (pin "2") (pinfunction "C_2") (pintype "passive"))
      (node (ref "R1") (pin "1") (pinfunction "1_1") (pintype "passive"))
      (node (ref "U1") (pin "1") (pinfunction "1_1") (pintype "passive"))
    )
    (net (code "41") (name "Net-(D2-C)") (class "Default")
      (node (ref "D2") (pin "2") (pinfunction "C_2") (pintype "passive"))
      (node (ref "R2") (pin "1") (pinfunction "1_1") (pintype "passive"))
      (node (ref "U2") (pin "1") (pinfunction "1_1") (pintype "passive"))
    )
    (net (code "42") (name "Net-(D3-C)") (class "Default")
      (node (ref "D3") (pin "2") (pinfunction "C_2") (pintype "passive"))
      (node (ref "R3") (pin "1") (pinfunction "1_1") (pintype "passive"))
      (node (ref "U3") (pin "1") (pinfunction "1_1") (pintype "passive"))
    )
    (net (code "43") (name "Net-(D4-C)") (class "Default")
      (node (ref "D4") (pin "2") (pinfunction "C_2") (pintype "passive"))
      (node (ref "R4") (pin "1") (pinfunction "1_1") (pintype "passive"))
      (node (ref "U4") (pin "1") (pinfunction "1_1") (pintype "passive"))
    )
    (net (code "44") (name "Net-(D5-C)") (class "Default")
      (node (ref "D5") (pin "2") (pinfunction "C_2") (pintype "passive"))
      (node (ref "R5") (pin "1") (pinfunction "1_1") (pintype "passive"))
      (node (ref "U5") (pin "1") (pinfunction "1_1") (pintype "passive"))
    )
    (net (code "45") (name "Net-(D6-C)") (class "Default")
      (node (ref "D6") (pin "2") (pinfunction "C_2") (pintype "passive"))
      (node (ref "R6") (pin "1") (pinfunction "1_1") (pintype "passive"))
      (node (ref "U6") (pin "1") (pinfunction "1_1") (pintype "passive"))
    )
    (net (code "46") (name "Net-(D7-C)") (class "Default")
      (node (ref "D7") (pin "2") (pinfunction "C_2") (pintype "passive"))
      (node (ref "R7") (pin "1") (pinfunction "1_1") (pintype "passive"))
      (node (ref "U7") (pin "1") (pinfunction "1_1") (pintype "passive"))
    )
    (net (code "47") (name "Net-(D8-C)") (class "Default")
      (node (ref "D8") (pin "2") (pinfunction "C_2") (pintype "passive"))
      (node (ref "R8") (pin "1") (pinfunction "1_1") (pintype "passive"))
      (node (ref "U8") (pin "1") (pinfunction "1_1") (pintype "passive"))
    )
    (net (code "48") (name "Net-(D9-C)") (class "Default")
      (node (ref "D9") (pin "2") (pinfunction "C_2") (pintype "passive"))
      (node (ref "R9") (pin "1") (pinfunction "1_1") (pintype "passive"))
      (node (ref "U9") (pin "1") (pinfunction "1_1") (pintype "passive"))
    )
    (net (code "49") (name "Net-(D10-C)") (class "Default")
      (node (ref "D10") (pin "2") (pinfunction "C_2") (pintype "passive"))
      (node (ref "R10") (pin "1") (pinfunction "1_1") (pintype "passive"))
      (node (ref "U10") (pin "1") (pinfunction "1_1") (pintype "passive"))
    )
    (net (code "50") (name "Net-(D11-C)") (class "Default")
      (node (ref "D11") (pin "2") (pinfunction "C_2") (pintype "passive"))
      (node (ref "R11") (pin "1") (pinfunction "1_1") (pintype "passive"))
      (node (ref "U11") (pin "1") (pinfunction "1_1") (pintype "passive"))
    )
    (net (code "51") (name "Net-(D12-C)") (class "Default")
      (node (ref "D12") (pin "2") (pinfunction "C_2") (pintype "passive"))
      (node (ref "R12") (pin "1") (pinfunction "1_1") (pintype "passive"))
      (node (ref "U12") (pin "1") (pinfunction "1_1") (pintype "passive"))
    )
    (net (code "52") (name "Net-(D13-C)") (class "Default")
      (node (ref "D13") (pin "2") (pinfunction "C_2") (pintype "passive"))
      (node (ref "R13") (pin "1") (pinfunction "1_1") (pintype "passive"))
      (node (ref "U13") (pin "1") (pinfunction "1_1") (pintype "passive"))
    )
    (net (code "53") (name "Net-(D14-C)") (class "Default")
      (node (ref "D14") (pin "2") (pinfunction "C_2") (pintype "passive"))
      (node (ref "R14") (pin "1") (pinfunction "1_1") (pintype "passive"))
      (node (ref "U14") (pin "1") (pinfunction "1_1") (pintype "passive"))
    )
    (net (code "54") (name "Net-(D15-C)") (class "Default")
      (node (ref "D15") (pin "2") (pinfunction "C_2") (pintype "passive"))
      (node (ref "R15") (pin "1") (pinfunction "1_1") (pintype "passive"))
      (node (ref "U15") (pin "1") (pinfunction "1_1") (pintype "passive"))
    )
    (net (code "55") (name "Net-(D16-C)") (class "Default")
      (node (ref "D16") (pin "2") (pinfunction "C_2") (pintype "passive"))
      (node (ref "R16") (pin "1") (pinfunction "1_1") (pintype "passive"))
      (node (ref "U16") (pin "1") (pinfunction "1_1") (pintype "passive"))
    )
    (net (code "56") (name "Net-(D17-C)") (class "Default")
      (node (ref "D17") (pin "2") (pinfunction "C_2") (pintype "passive"))
      (node (ref "R17") (pin "1") (pinfunction "1_1") (pintype "passive"))
      (node (ref "U17") (pin "1") (pinfunction "1_1") (pintype "passive"))
    )
    (net (code "57") (name "Net-(D23-A)") (class "Default")
      (node (ref "D23") (pin "1") (pinfunction "A_1") (pintype "passive"))
      (node (ref "D24") (pin "2") (pinfunction "C_2") (pintype "passive"))
      (node (ref "F1") (pin "2") (pinfunction "2_2") (pintype "passive"))
      (node (ref "F1") (pin "4") (pinfunction "4_4") (pintype "passive"))
      (node (ref "M1") (pin "2") (pinfunction "2_2") (pintype "passive"))
    )
    (net (code "58") (name "Net-(D23-C)") (class "Default")
      (node (ref "C3") (pin "1") (pinfunction "1_1") (pintype "passive"))
      (node (ref "C8") (pin "1") (pinfunction "1_1") (pintype "passive"))
      (node (ref "D23") (pin "2") (pinfunction "C_2") (pintype "passive"))
      (node (ref "R23") (pin "2") (pinfunction "2_2") (pintype "passive"))
      (node (ref "U24") (pin "8") (pinfunction "VCC_8") (pintype "power_in"))
    )
    (net (code "59") (name "Net-(D25-C)") (class "Default")
      (node (ref "D25") (pin "1") (pinfunction "C_1") (pintype "passive"))
      (node (ref "L1") (pin "1") (pinfunction "1_1") (pintype "passive"))
      (node (ref "U24") (pin "1") (pinfunction "OUT_1") (pintype "output"))
    )
    (net (code "60") (name "Net-(J1-Pad1)") (class "Default")
      (node (ref "J1") (pin "1") (pinfunction "1_1") (pintype "passive"))
      (node (ref "R1") (pin "2") (pinfunction "2_2") (pintype "passive"))
    )
    (net (code "61") (name "Net-(J2-Pad1)") (class "Default")
      (node (ref "J2") (pin "1") (pinfunction "1_1") (pintype "passive"))
      (node (ref "R4") (pin "2") (pinfunction "2_2") (pintype "passive"))
    )
    (net (code "62") (name "Net-(J2-Pad2)") (class "Default")
      (node (ref "J2") (pin "2") (pinfunction "2_2") (pintype "passive"))
      (node (ref "R3") (pin "2") (pinfunction "2_2") (pintype "passive"))
    )
    (net (code "63") (name "Net-(J2-Pad3)") (class "Default")
      (node (ref "J2") (pin "3") (pinfunction "3_3") (pintype "passive"))
      (node (ref "R2") (pin "2") (pinfunction "2_2") (pintype "passive"))
    )
    (net (code "64") (name "Net-(J3-Pad2)") (class "Default")
      (node (ref "J3") (pin "2") (pinfunction "2_2") (pintype "passive"))
      (node (ref "R6") (pin "2") (pinfunction "2_2") (pintype "passive"))
    )
    (net (code "65") (name "Net-(J3-Pad3)") (class "Default")
      (node (ref "J3") (pin "3") (pinfunction "3_3") (pintype "passive"))
      (node (ref "R5") (pin "2") (pinfunction "2_2") (pintype "passive"))
    )
    (net (code "66") (name "Net-(J4-Pad2)") (class "Default")
      (node (ref "J4") (pin "2") (pinfunction "2_2") (pintype "passive"))
      (node (ref "R8") (pin "2") (pinfunction "2_2") (pintype "passive"))
    )
    (net (code "67") (name "Net-(J4-Pad3)") (class "Default")
      (node (ref "J4") (pin "3") (pinfunction "3_3") (pintype "passive"))
      (node (ref "R7") (pin "2") (pinfunction "2_2") (pintype "passive"))
    )
    (net (code "68") (name "Net-(J5-Pad1)") (class "Default")
      (node (ref "J5") (pin "1") (pinfunction "1_1") (pintype "passive"))
      (node (ref "R12") (pin "2") (pinfunction "2_2") (pintype "passive"))
    )
    (net (code "69") (name "Net-(J5-Pad2)") (class "Default")
      (node (ref "J5") (pin "2") (pinfunction "2_2") (pintype "passive"))
      (node (ref "R11") (pin "2") (pinfunction "2_2") (pintype "passive"))
    )
    (net (code "70") (name "Net-(J5-Pad3)") (class "Default")
      (node (ref "J5") (pin "3") (pinfunction "3_3") (pintype "passive"))
      (node (ref "R10") (pin "2") (pinfunction "2_2") (pintype "passive"))
    )
    (net (code "71") (name "Net-(J6-Pad2)") (class "Default")
      (node (ref "J6") (pin "2") (pinfunction "2_2") (pintype "passive"))
      (node (ref "R14") (pin "2") (pinfunction "2_2") (pintype "passive"))
    )
    (net (code "72") (name "Net-(J6-Pad3)") (class "Default")
      (node (ref "J6") (pin "3") (pinfunction "3_3") (pintype "passive"))
      (node (ref "R13") (pin "2") (pinfunction "2_2") (pintype "passive"))
    )
    (net (code "73") (name "Net-(J7-Pad1)") (class "Default")
      (node (ref "J7") (pin "1") (pinfunction "1_1") (pintype "passive"))
      (node (ref "R17") (pin "2") (pinfunction "2_2") (pintype "passive"))
    )
    (net (code "74") (name "Net-(J7-Pad2)") (class "Default")
      (node (ref "J7") (pin "2") (pinfunction "2_2") (pintype "passive"))
      (node (ref "R16") (pin "2") (pinfunction "2_2") (pintype "passive"))
    )
    (net (code "75") (name "Net-(J7-Pad3)") (class "Default")
      (node (ref "J7") (pin "3") (pinfunction "3_3") (pintype "passive"))
      (node (ref "R15") (pin "2") (pinfunction "2_2") (pintype "passive"))
    )
    (net (code "76") (name "Net-(U24-COMP)") (class "Default")
      (node (ref "C6") (pin "2") (pinfunction "2_2") (pintype "passive"))
      (node (ref "C7") (pin "2") (pinfunction "2_2") (pintype "passive"))
      (node (ref "U24") (pin "4") (pinfunction "COMP_4") (pintype "output"))
    )
    (net (code "77") (name "Net-(U24-FB)") (class "Default")
      (node (ref "R24") (pin "1") (pinfunction "1_1") (pintype "passive"))
      (node (ref "R26") (pin "2") (pinfunction "2_2") (pintype "passive"))
      (node (ref "U24") (pin "5") (pinfunction "FB_5") (pintype "input"))
    )
    (net (code "78") (name "Net-(U24-VREF)") (class "Default")
      (node (ref "TP2") (pin "1") (pinfunction "1_1") (pintype "passive"))
      (node (ref "U24") (pin "6") (pinfunction "VREF_6") (pintype "output"))
    )
    (net (code "79") (name "VCC3v3") (class "Default")
      (node (ref "C1") (pin "1") (pinfunction "1_1") (pintype "passive"))
      (node (ref "C4") (pin "1") (pinfunction "1_1") (pintype "passive"))
      (node (ref "R31") (pin "2") (pinfunction "2_2") (pintype "passive"))
      (node (ref "R32") (pin "2") (pinfunction "2_2") (pintype "passive"))
      (node (ref "R33") (pin "2") (pinfunction "2_2") (pintype "passive"))
      (node (ref "R34") (pin "2") (pinfunction "2_2") (pintype "passive"))
      (node (ref "R35") (pin "2") (pinfunction "2_2") (pintype "passive"))
      (node (ref "R36") (pin "2") (pinfunction "2_2") (pintype "passive"))
      (node (ref "R37") (pin "2") (pinfunction "2_2") (pintype "passive"))
      (node (ref "R38") (pin "2") (pinfunction "2_2") (pintype "passive"))
      (node (ref "R39") (pin "2") (pinfunction "2_2") (pintype "passive"))
      (node (ref "R40") (pin "2") (pinfunction "2_2") (pintype "passive"))
      (node (ref "R41") (pin "2") (pinfunction "2_2") (pintype "passive"))
      (node (ref "R42") (pin "2") (pinfunction "2_2") (pintype "passive"))
      (node (ref "R43") (pin "2") (pinfunction "2_2") (pintype "passive"))
      (node (ref "R44") (pin "2") (pinfunction "2_2") (pintype "passive"))
      (node (ref "R45") (pin "2") (pinfunction "2_2") (pintype "passive"))
      (node (ref "R46") (pin "2") (pinfunction "2_2") (pintype "passive"))
      (node (ref "R47") (pin "2") (pinfunction "2_2") (pintype "passive"))
      (node (ref "U23") (pin "2") (pinfunction "VOUT_2") (pintype "power_in"))
      (node (ref "U23") (pin "4") (pinfunction "VOUT_4") (pintype "power_in"))
      (node (ref "U25") (pin "2") (pinfunction "OUT_2") (pintype "power_in"))
      (node (ref "U25") (pin "4") (pinfunction "TAB_4") (pintype "power_in"))
    )
    (net (code "80") (name "VCC5") (class "Default")
      (node (ref "C2") (pin "1") (pinfunction "1_1") (pintype "passive"))
      (node (ref "C5") (pin "1") (pinfunction "1_1") (pintype "passive"))
      (node (ref "C9") (pin "1") (pinfunction "1_1") (pintype "passive"))
      (node (ref "L1") (pin "2") (pinfunction "2_2") (pintype "passive"))
      (node (ref "R24") (pin "2") (pinfunction "2_2") (pintype "passive"))
      (node (ref "U23") (pin "3") (pinfunction "VIN_3") (pintype "power_in"))
      (node (ref "U25") (pin "3") (pinfunction "IN_3") (pintype "power_in"))
    )
    (net (code "81") (name "VCC24") (class "Default")
      (node (ref "F1") (pin "1") (pinfunction "1_1") (pintype "passive"))
      (node (ref "F1") (pin "3") (pinfunction "3_3") (pintype "passive"))
      (node (ref "J1") (pin "3") (pinfunction "3_3") (pintype "passive"))
    )
    (net (code "82") (name "unconnected-(U24-SYNC-Pad2)") (class "Default")
      (node (ref "U24") (pin "2") (pinfunction "SYNC_2") (pintype "input+no_connect"))
    )
  )
)
